# untitled.net
KiCad netlist of a schematic drawn in EAGLE
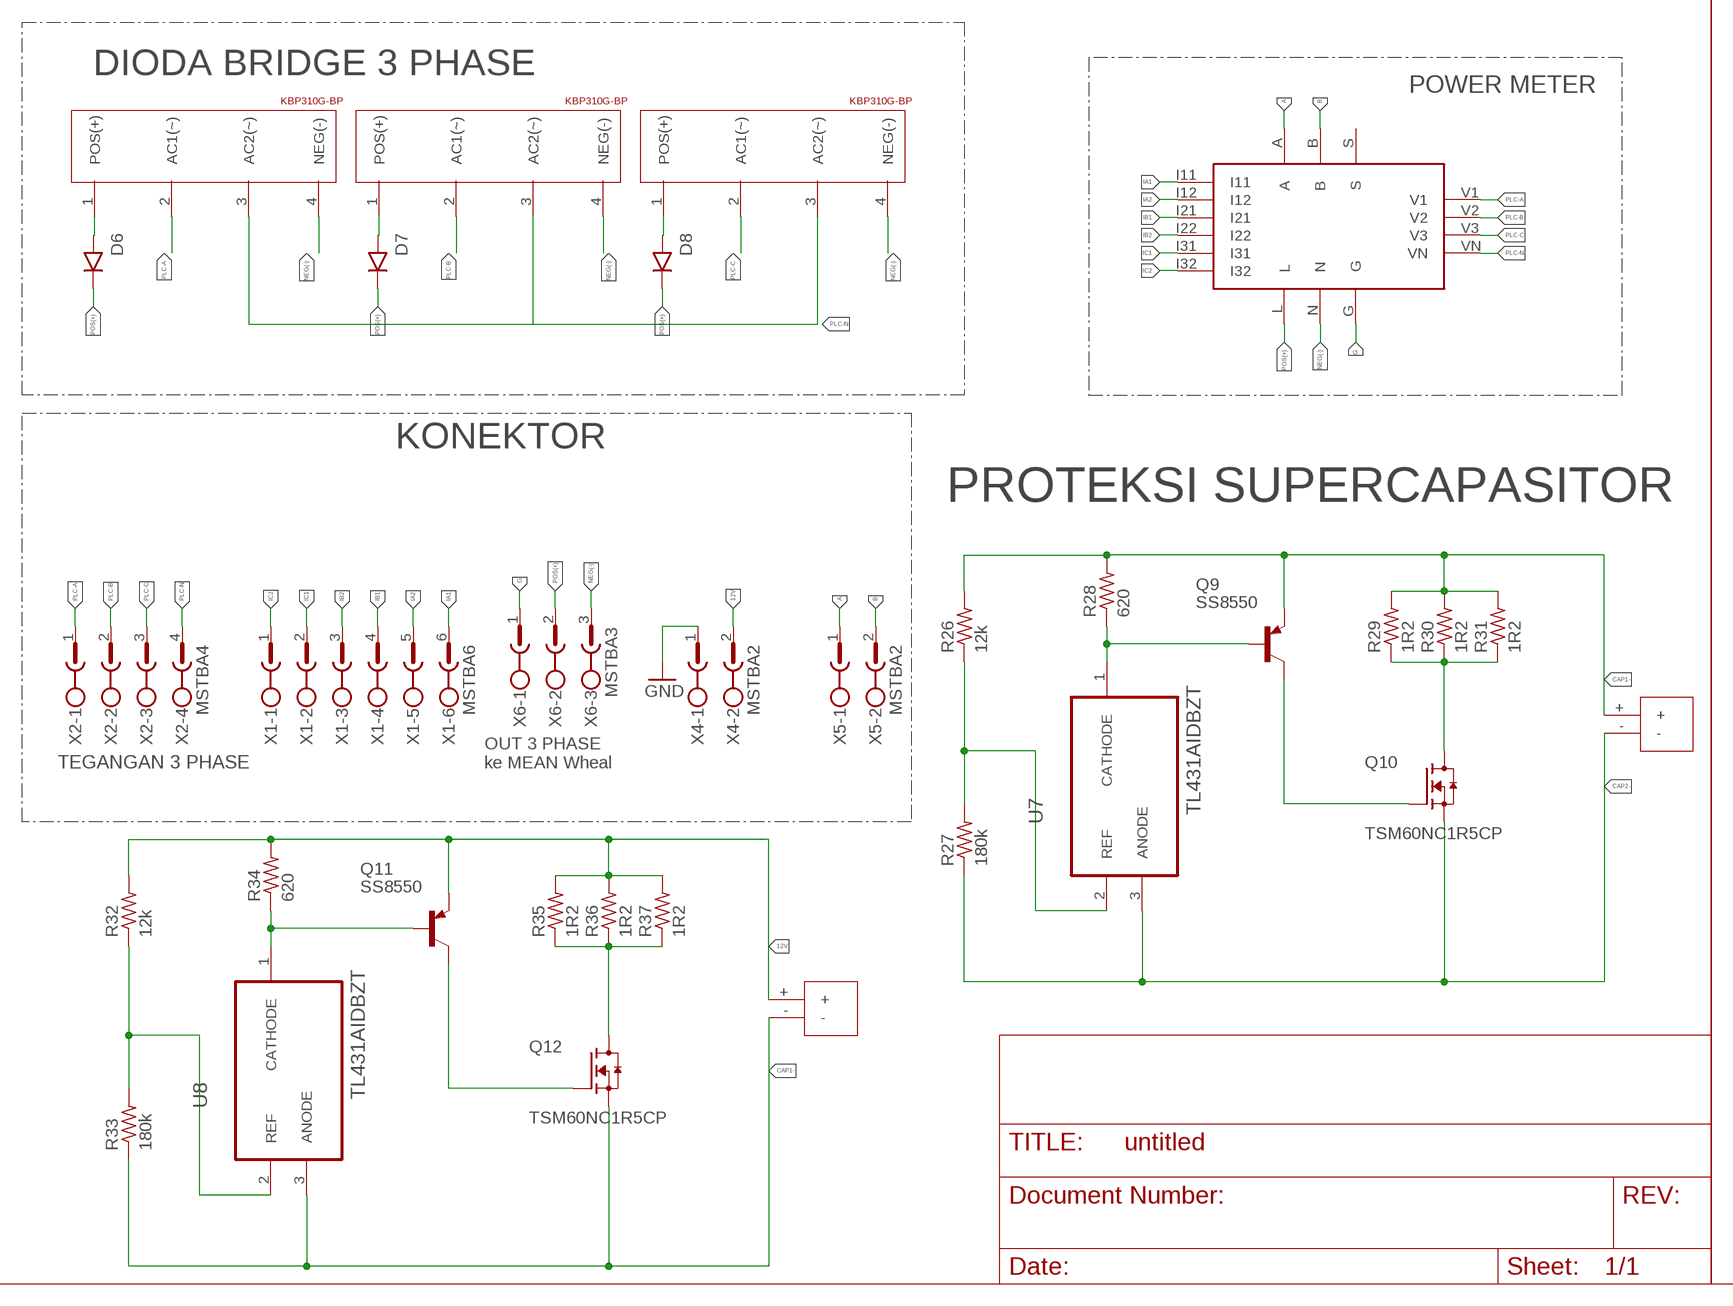
[diagram p0: schematic, sheet 1, part 1 of 2]
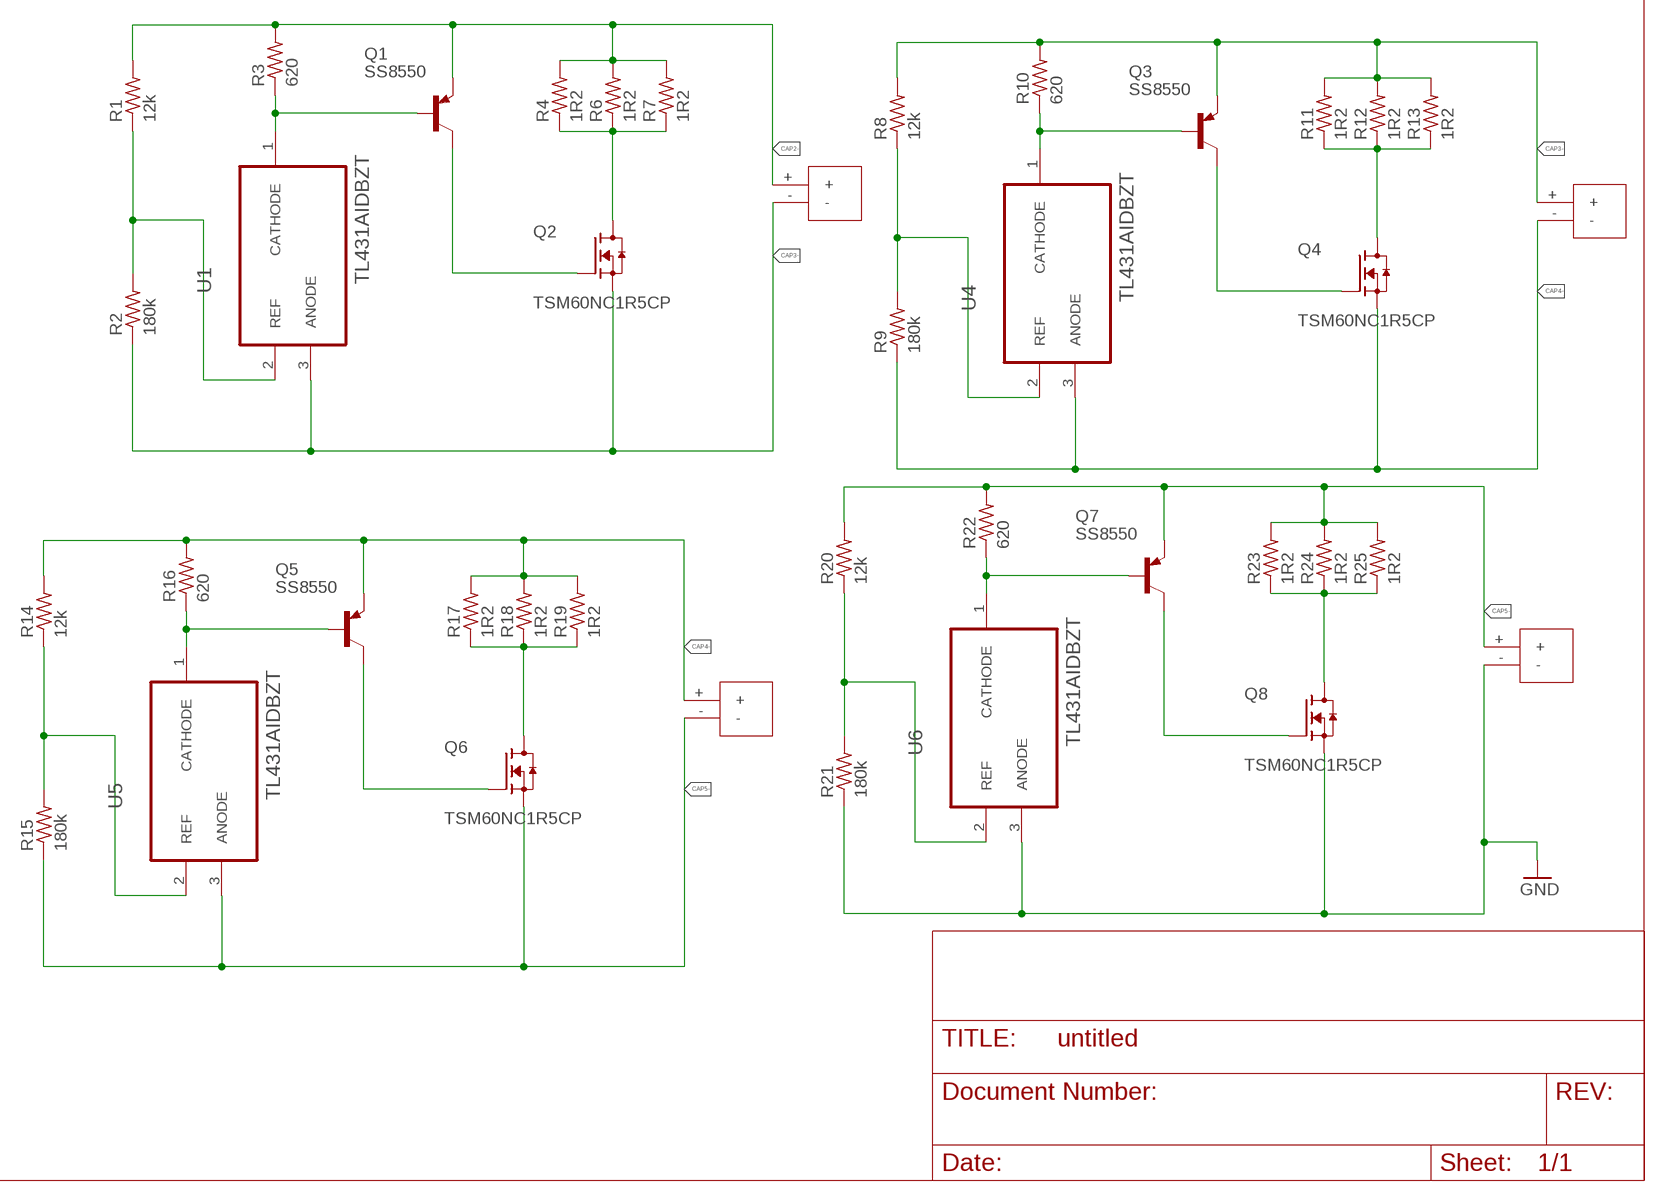
[diagram p1: schematic, sheet 1, part 2 of 2]

(export (version "E")
  (design (tool "Eeschema 10.0.6"))
  (components
    (comp (ref "D6")
      (value "1N4001")
      (footprint "eagle-import:DO41-10")
      (fields (field (name "MF") "HVCA"))
      (libsource (lib "eagle-import") (part "1N4001"))
    )
    (comp (ref "D7")
      (value "1N4001")
      (footprint "eagle-import:DO41-10")
      (fields (field (name "MF") "HVCA"))
      (libsource (lib "eagle-import") (part "1N4001"))
    )
    (comp (ref "D8")
      (value "1N4001")
      (footprint "eagle-import:DO41-10")
      (fields (field (name "MF") "HVCA"))
      (libsource (lib "eagle-import") (part "1N4001"))
    )
    (comp (ref "POWERMETER1")
      (value "POWERMETER")
      (footprint "eagle-import:POWERMETER")
      (libsource (lib "eagle-import") (part "POWERMETER"))
    )
    (comp (ref "Q1")
      (value "SS8550")
      (footprint "eagle-import:SOT-23_BEC")
      (fields (field (name "MF") "ON Semiconductor / Fairchild"))
      (libsource (lib "eagle-import") (part "SS8550"))
    )
    (comp (ref "Q2")
      (value "TSM60NC1R5CP")
      (footprint "eagle-import:TRANS_TSM60NC1R5CP")
      (fields (field (name "MF") "Taiwan Semiconductor"))
      (libsource (lib "eagle-import") (part "TSM60NC1R5CP"))
    )
    (comp (ref "Q3")
      (value "SS8550")
      (footprint "eagle-import:SOT-23_BEC")
      (fields (field (name "MF") "ON Semiconductor / Fairchild"))
      (libsource (lib "eagle-import") (part "SS8550"))
    )
    (comp (ref "Q4")
      (value "TSM60NC1R5CP")
      (footprint "eagle-import:TRANS_TSM60NC1R5CP")
      (fields (field (name "MF") "Taiwan Semiconductor"))
      (libsource (lib "eagle-import") (part "TSM60NC1R5CP"))
    )
    (comp (ref "Q5")
      (value "SS8550")
      (footprint "eagle-import:SOT-23_BEC")
      (fields (field (name "MF") "ON Semiconductor / Fairchild"))
      (libsource (lib "eagle-import") (part "SS8550"))
    )
    (comp (ref "Q6")
      (value "TSM60NC1R5CP")
      (footprint "eagle-import:TRANS_TSM60NC1R5CP")
      (fields (field (name "MF") "Taiwan Semiconductor"))
      (libsource (lib "eagle-import") (part "TSM60NC1R5CP"))
    )
    (comp (ref "Q7")
      (value "SS8550")
      (footprint "eagle-import:SOT-23_BEC")
      (fields (field (name "MF") "ON Semiconductor / Fairchild"))
      (libsource (lib "eagle-import") (part "SS8550"))
    )
    (comp (ref "Q8")
      (value "TSM60NC1R5CP")
      (footprint "eagle-import:TRANS_TSM60NC1R5CP")
      (fields (field (name "MF") "Taiwan Semiconductor"))
      (libsource (lib "eagle-import") (part "TSM60NC1R5CP"))
    )
    (comp (ref "Q9")
      (value "SS8550")
      (footprint "eagle-import:SOT-23_BEC")
      (fields (field (name "MF") "ON Semiconductor / Fairchild"))
      (libsource (lib "eagle-import") (part "SS8550"))
    )
    (comp (ref "Q10")
      (value "TSM60NC1R5CP")
      (footprint "eagle-import:TRANS_TSM60NC1R5CP")
      (fields (field (name "MF") "Taiwan Semiconductor"))
      (libsource (lib "eagle-import") (part "TSM60NC1R5CP"))
    )
    (comp (ref "Q11")
      (value "SS8550")
      (footprint "eagle-import:SOT-23_BEC")
      (fields (field (name "MF") "ON Semiconductor / Fairchild"))
      (libsource (lib "eagle-import") (part "SS8550"))
    )
    (comp (ref "Q12")
      (value "TSM60NC1R5CP")
      (footprint "eagle-import:TRANS_TSM60NC1R5CP")
      (fields (field (name "MF") "Taiwan Semiconductor"))
      (libsource (lib "eagle-import") (part "TSM60NC1R5CP"))
    )
    (comp (ref "R1")
      (value "12k")
      (footprint "eagle-import:R0805")
      (libsource (lib "eagle-import") (part "R-US_R0805"))
    )
    (comp (ref "R2")
      (value "180k")
      (footprint "eagle-import:R0805")
      (libsource (lib "eagle-import") (part "R-US_R0805"))
    )
    (comp (ref "R3")
      (value "620")
      (footprint "eagle-import:R0805")
      (libsource (lib "eagle-import") (part "R-US_R0805"))
    )
    (comp (ref "R4")
      (value "1R2")
      (footprint "eagle-import:R2512")
      (libsource (lib "eagle-import") (part "rcl_334_R-US_R2512"))
    )
    (comp (ref "R6")
      (value "1R2")
      (footprint "eagle-import:R2512")
      (libsource (lib "eagle-import") (part "rcl_334_R-US_R2512"))
    )
    (comp (ref "R7")
      (value "1R2")
      (footprint "eagle-import:R2512")
      (libsource (lib "eagle-import") (part "rcl_334_R-US_R2512"))
    )
    (comp (ref "R8")
      (value "12k")
      (footprint "eagle-import:R0805")
      (libsource (lib "eagle-import") (part "R-US_R0805"))
    )
    (comp (ref "R9")
      (value "180k")
      (footprint "eagle-import:R0805")
      (libsource (lib "eagle-import") (part "R-US_R0805"))
    )
    (comp (ref "R10")
      (value "620")
      (footprint "eagle-import:R0805")
      (libsource (lib "eagle-import") (part "R-US_R0805"))
    )
    (comp (ref "R11")
      (value "1R2")
      (footprint "eagle-import:R2512")
      (libsource (lib "eagle-import") (part "rcl_334_R-US_R2512"))
    )
    (comp (ref "R12")
      (value "1R2")
      (footprint "eagle-import:R2512")
      (libsource (lib "eagle-import") (part "rcl_334_R-US_R2512"))
    )
    (comp (ref "R13")
      (value "1R2")
      (footprint "eagle-import:R2512")
      (libsource (lib "eagle-import") (part "rcl_334_R-US_R2512"))
    )
    (comp (ref "R14")
      (value "12k")
      (footprint "eagle-import:R0805")
      (libsource (lib "eagle-import") (part "R-US_R0805"))
    )
    (comp (ref "R15")
      (value "180k")
      (footprint "eagle-import:R0805")
      (libsource (lib "eagle-import") (part "R-US_R0805"))
    )
    (comp (ref "R16")
      (value "620")
      (footprint "eagle-import:R0805")
      (libsource (lib "eagle-import") (part "R-US_R0805"))
    )
    (comp (ref "R17")
      (value "1R2")
      (footprint "eagle-import:R2512")
      (libsource (lib "eagle-import") (part "rcl_334_R-US_R2512"))
    )
    (comp (ref "R18")
      (value "1R2")
      (footprint "eagle-import:R2512")
      (libsource (lib "eagle-import") (part "rcl_334_R-US_R2512"))
    )
    (comp (ref "R19")
      (value "1R2")
      (footprint "eagle-import:R2512")
      (libsource (lib "eagle-import") (part "rcl_334_R-US_R2512"))
    )
    (comp (ref "R20")
      (value "12k")
      (footprint "eagle-import:R0805")
      (libsource (lib "eagle-import") (part "R-US_R0805"))
    )
    (comp (ref "R21")
      (value "180k")
      (footprint "eagle-import:R0805")
      (libsource (lib "eagle-import") (part "R-US_R0805"))
    )
    (comp (ref "R22")
      (value "620")
      (footprint "eagle-import:R0805")
      (libsource (lib "eagle-import") (part "R-US_R0805"))
    )
    (comp (ref "R23")
      (value "1R2")
      (footprint "eagle-import:R2512")
      (libsource (lib "eagle-import") (part "rcl_334_R-US_R2512"))
    )
    (comp (ref "R24")
      (value "1R2")
      (footprint "eagle-import:R2512")
      (libsource (lib "eagle-import") (part "rcl_334_R-US_R2512"))
    )
    (comp (ref "R25")
      (value "1R2")
      (footprint "eagle-import:R2512")
      (libsource (lib "eagle-import") (part "rcl_334_R-US_R2512"))
    )
    (comp (ref "R26")
      (value "12k")
      (footprint "eagle-import:R0805")
      (libsource (lib "eagle-import") (part "R-US_R0805"))
    )
    (comp (ref "R27")
      (value "180k")
      (footprint "eagle-import:R0805")
      (libsource (lib "eagle-import") (part "R-US_R0805"))
    )
    (comp (ref "R28")
      (value "620")
      (footprint "eagle-import:R0805")
      (libsource (lib "eagle-import") (part "R-US_R0805"))
    )
    (comp (ref "R29")
      (value "1R2")
      (footprint "eagle-import:R2512")
      (libsource (lib "eagle-import") (part "rcl_334_R-US_R2512"))
    )
    (comp (ref "R30")
      (value "1R2")
      (footprint "eagle-import:R2512")
      (libsource (lib "eagle-import") (part "rcl_334_R-US_R2512"))
    )
    (comp (ref "R31")
      (value "1R2")
      (footprint "eagle-import:R2512")
      (libsource (lib "eagle-import") (part "rcl_334_R-US_R2512"))
    )
    (comp (ref "R32")
      (value "12k")
      (footprint "eagle-import:R0805")
      (libsource (lib "eagle-import") (part "R-US_R0805"))
    )
    (comp (ref "R33")
      (value "180k")
      (footprint "eagle-import:R0805")
      (libsource (lib "eagle-import") (part "R-US_R0805"))
    )
    (comp (ref "R34")
      (value "620")
      (footprint "eagle-import:R0805")
      (libsource (lib "eagle-import") (part "R-US_R0805"))
    )
    (comp (ref "R35")
      (value "1R2")
      (footprint "eagle-import:R2512")
      (libsource (lib "eagle-import") (part "rcl_334_R-US_R2512"))
    )
    (comp (ref "R36")
      (value "1R2")
      (footprint "eagle-import:R2512")
      (libsource (lib "eagle-import") (part "rcl_334_R-US_R2512"))
    )
    (comp (ref "R37")
      (value "1R2")
      (footprint "eagle-import:R2512")
      (libsource (lib "eagle-import") (part "rcl_334_R-US_R2512"))
    )
    (comp (ref "SUPERCAP1")
      (value "2.7/500F")
      (footprint "eagle-import:SUPERCAP")
      (libsource (lib "eagle-import") (part "SUPERCAP"))
    )
    (comp (ref "SUPERCAP2")
      (value "2.7/500F")
      (footprint "eagle-import:SUPERCAP")
      (libsource (lib "eagle-import") (part "SUPERCAP"))
    )
    (comp (ref "SUPERCAP3")
      (value "2.7/500F")
      (footprint "eagle-import:SUPERCAP")
      (libsource (lib "eagle-import") (part "SUPERCAP"))
    )
    (comp (ref "SUPERCAP4")
      (value "2.7/500F")
      (footprint "eagle-import:SUPERCAP")
      (libsource (lib "eagle-import") (part "SUPERCAP"))
    )
    (comp (ref "SUPERCAP5")
      (value "2.7/500F")
      (footprint "eagle-import:SUPERCAP")
      (libsource (lib "eagle-import") (part "SUPERCAP"))
    )
    (comp (ref "SUPERCAP6")
      (value "2.7/500F")
      (footprint "eagle-import:SUPERCAP")
      (libsource (lib "eagle-import") (part "SUPERCAP"))
    )
    (comp (ref "U$1")
      (value "KBP310G-BP")
      (footprint "eagle-import:KBP310G-BP")
      (fields (field (name "MF") "Micro Commercial"))
      (libsource (lib "eagle-import") (part "KBP310G-BP"))
    )
    (comp (ref "U$2")
      (value "KBP310G-BP")
      (footprint "eagle-import:KBP310G-BP")
      (fields (field (name "MF") "Micro Commercial"))
      (libsource (lib "eagle-import") (part "KBP310G-BP"))
    )
    (comp (ref "U$3")
      (value "KBP310G-BP")
      (footprint "eagle-import:KBP310G-BP")
      (fields (field (name "MF") "Micro Commercial"))
      (libsource (lib "eagle-import") (part "KBP310G-BP"))
    )
    (comp (ref "U1")
      (value "TL431AIDBZT")
      (footprint "eagle-import:SOT95P237X112-3N")
      (fields (field (name "MF") "Texas Instruments"))
      (libsource (lib "eagle-import") (part "TL431AIDBZT"))
    )
    (comp (ref "U4")
      (value "TL431AIDBZT")
      (footprint "eagle-import:SOT95P237X112-3N")
      (fields (field (name "MF") "Texas Instruments"))
      (libsource (lib "eagle-import") (part "TL431AIDBZT"))
    )
    (comp (ref "U5")
      (value "TL431AIDBZT")
      (footprint "eagle-import:SOT95P237X112-3N")
      (fields (field (name "MF") "Texas Instruments"))
      (libsource (lib "eagle-import") (part "TL431AIDBZT"))
    )
    (comp (ref "U6")
      (value "TL431AIDBZT")
      (footprint "eagle-import:SOT95P237X112-3N")
      (fields (field (name "MF") "Texas Instruments"))
      (libsource (lib "eagle-import") (part "TL431AIDBZT"))
    )
    (comp (ref "U7")
      (value "TL431AIDBZT")
      (footprint "eagle-import:SOT95P237X112-3N")
      (fields (field (name "MF") "Texas Instruments"))
      (libsource (lib "eagle-import") (part "TL431AIDBZT"))
    )
    (comp (ref "U8")
      (value "TL431AIDBZT")
      (footprint "eagle-import:SOT95P237X112-3N")
      (fields (field (name "MF") "Texas Instruments"))
      (libsource (lib "eagle-import") (part "TL431AIDBZT"))
    )
    (comp (ref "X1")
      (value "MSTBA6")
      (footprint "eagle-import:MSTBA6")
      (fields (field (name "MF") "FARNELL") (field (name "MPN") "1757284"))
      (libsource (lib "eagle-import") (part "MSTBA6"))
    )
    (comp (ref "X2")
      (value "MSTBA4")
      (footprint "eagle-import:MSTBA4")
      (fields (field (name "MF") "FARNELL") (field (name "MPN") "1757268"))
      (libsource (lib "eagle-import") (part "MSTBA4"))
    )
    (comp (ref "X4")
      (value "MSTBA2")
      (footprint "eagle-import:MSTBA2")
      (fields (field (name "MF") "FARNELL") (field (name "MPN") "1757242"))
      (libsource (lib "eagle-import") (part "MSTBA2"))
    )
    (comp (ref "X5")
      (value "MSTBA2")
      (footprint "eagle-import:MSTBA2")
      (fields (field (name "MF") "FARNELL") (field (name "MPN") "1757242"))
      (libsource (lib "eagle-import") (part "MSTBA2"))
    )
    (comp (ref "X6")
      (value "MSTBA3")
      (footprint "eagle-import:MSTBA3")
      (fields (field (name "MF") "FARNELL") (field (name "MPN") "1757255"))
      (libsource (lib "eagle-import") (part "MSTBA3"))
    )
  )
  (nets
    (net (code "1") (name "12V") (class "Default")
      (node (ref "Q11") (pin "E") (pinfunction "E_E") (pintype "passive"))
      (node (ref "R32") (pin "2") (pinfunction "2_2") (pintype "passive"))
      (node (ref "R34") (pin "2") (pinfunction "2_2") (pintype "passive"))
      (node (ref "R35") (pin "2") (pinfunction "2_2") (pintype "passive"))
      (node (ref "R36") (pin "2") (pinfunction "2_2") (pintype "passive"))
      (node (ref "R37") (pin "2") (pinfunction "2_2") (pintype "passive"))
      (node (ref "SUPERCAP6") (pin "+") (pinfunction "+_+") (pintype "bidirectional"))
      (node (ref "X4") (pin "2") (pinfunction "1_2") (pintype "passive"))
    )
    (net (code "2") (name "A") (class "Default")
      (node (ref "POWERMETER1") (pin "A") (pinfunction "A_A") (pintype "bidirectional"))
      (node (ref "X5") (pin "1") (pinfunction "1_1") (pintype "passive"))
    )
    (net (code "3") (name "B") (class "Default")
      (node (ref "POWERMETER1") (pin "B") (pinfunction "B_B") (pintype "bidirectional"))
      (node (ref "X5") (pin "2") (pinfunction "1_2") (pintype "passive"))
    )
    (net (code "4") (name "CAP1-") (class "Default")
      (node (ref "Q12") (pin "3") (pinfunction "S_3") (pintype "passive"))
      (node (ref "Q9") (pin "E") (pinfunction "E_E") (pintype "passive"))
      (node (ref "R26") (pin "2") (pinfunction "2_2") (pintype "passive"))
      (node (ref "R28") (pin "2") (pinfunction "2_2") (pintype "passive"))
      (node (ref "R29") (pin "2") (pinfunction "2_2") (pintype "passive"))
      (node (ref "R30") (pin "2") (pinfunction "2_2") (pintype "passive"))
      (node (ref "R31") (pin "2") (pinfunction "2_2") (pintype "passive"))
      (node (ref "R33") (pin "1") (pinfunction "1_1") (pintype "passive"))
      (node (ref "SUPERCAP5") (pin "+") (pinfunction "+_+") (pintype "bidirectional"))
      (node (ref "SUPERCAP6") (pin "-") (pinfunction "-_-") (pintype "bidirectional"))
      (node (ref "U8") (pin "3") (pinfunction "ANODE_3") (pintype "passive"))
    )
    (net (code "5") (name "CAP2-") (class "Default")
      (node (ref "Q1") (pin "E") (pinfunction "E_E") (pintype "passive"))
      (node (ref "Q10") (pin "3") (pinfunction "S_3") (pintype "passive"))
      (node (ref "R1") (pin "2") (pinfunction "2_2") (pintype "passive"))
      (node (ref "R27") (pin "1") (pinfunction "1_1") (pintype "passive"))
      (node (ref "R3") (pin "2") (pinfunction "2_2") (pintype "passive"))
      (node (ref "R4") (pin "2") (pinfunction "2_2") (pintype "passive"))
      (node (ref "R6") (pin "2") (pinfunction "2_2") (pintype "passive"))
      (node (ref "R7") (pin "2") (pinfunction "2_2") (pintype "passive"))
      (node (ref "SUPERCAP1") (pin "+") (pinfunction "+_+") (pintype "bidirectional"))
      (node (ref "SUPERCAP5") (pin "-") (pinfunction "-_-") (pintype "bidirectional"))
      (node (ref "U7") (pin "3") (pinfunction "ANODE_3") (pintype "passive"))
    )
    (net (code "6") (name "CAP3-") (class "Default")
      (node (ref "Q2") (pin "3") (pinfunction "S_3") (pintype "passive"))
      (node (ref "Q3") (pin "E") (pinfunction "E_E") (pintype "passive"))
      (node (ref "R10") (pin "2") (pinfunction "2_2") (pintype "passive"))
      (node (ref "R11") (pin "2") (pinfunction "2_2") (pintype "passive"))
      (node (ref "R12") (pin "2") (pinfunction "2_2") (pintype "passive"))
      (node (ref "R13") (pin "2") (pinfunction "2_2") (pintype "passive"))
      (node (ref "R2") (pin "1") (pinfunction "1_1") (pintype "passive"))
      (node (ref "R8") (pin "2") (pinfunction "2_2") (pintype "passive"))
      (node (ref "SUPERCAP1") (pin "-") (pinfunction "-_-") (pintype "bidirectional"))
      (node (ref "SUPERCAP2") (pin "+") (pinfunction "+_+") (pintype "bidirectional"))
      (node (ref "U1") (pin "3") (pinfunction "ANODE_3") (pintype "passive"))
    )
    (net (code "7") (name "CAP4-") (class "Default")
      (node (ref "Q4") (pin "3") (pinfunction "S_3") (pintype "passive"))
      (node (ref "Q5") (pin "E") (pinfunction "E_E") (pintype "passive"))
      (node (ref "R14") (pin "2") (pinfunction "2_2") (pintype "passive"))
      (node (ref "R16") (pin "2") (pinfunction "2_2") (pintype "passive"))
      (node (ref "R17") (pin "2") (pinfunction "2_2") (pintype "passive"))
      (node (ref "R18") (pin "2") (pinfunction "2_2") (pintype "passive"))
      (node (ref "R19") (pin "2") (pinfunction "2_2") (pintype "passive"))
      (node (ref "R9") (pin "1") (pinfunction "1_1") (pintype "passive"))
      (node (ref "SUPERCAP2") (pin "-") (pinfunction "-_-") (pintype "bidirectional"))
      (node (ref "SUPERCAP3") (pin "+") (pinfunction "+_+") (pintype "bidirectional"))
      (node (ref "U4") (pin "3") (pinfunction "ANODE_3") (pintype "passive"))
    )
    (net (code "8") (name "CAP5-") (class "Default")
      (node (ref "Q6") (pin "3") (pinfunction "S_3") (pintype "passive"))
      (node (ref "Q7") (pin "E") (pinfunction "E_E") (pintype "passive"))
      (node (ref "R15") (pin "1") (pinfunction "1_1") (pintype "passive"))
      (node (ref "R20") (pin "2") (pinfunction "2_2") (pintype "passive"))
      (node (ref "R22") (pin "2") (pinfunction "2_2") (pintype "passive"))
      (node (ref "R23") (pin "2") (pinfunction "2_2") (pintype "passive"))
      (node (ref "R24") (pin "2") (pinfunction "2_2") (pintype "passive"))
      (node (ref "R25") (pin "2") (pinfunction "2_2") (pintype "passive"))
      (node (ref "SUPERCAP3") (pin "-") (pinfunction "-_-") (pintype "bidirectional"))
      (node (ref "SUPERCAP4") (pin "+") (pinfunction "+_+") (pintype "bidirectional"))
      (node (ref "U5") (pin "3") (pinfunction "ANODE_3") (pintype "passive"))
    )
    (net (code "9") (name "G") (class "Default")
      (node (ref "POWERMETER1") (pin "G") (pinfunction "G_G") (pintype "bidirectional"))
      (node (ref "X6") (pin "1") (pinfunction "1_1") (pintype "passive"))
    )
    (net (code "10") (name "GND") (class "Default")
      (node (ref "Q8") (pin "3") (pinfunction "S_3") (pintype "passive"))
      (node (ref "R21") (pin "1") (pinfunction "1_1") (pintype "passive"))
      (node (ref "SUPERCAP4") (pin "-") (pinfunction "-_-") (pintype "bidirectional"))
      (node (ref "U6") (pin "3") (pinfunction "ANODE_3") (pintype "passive"))
      (node (ref "X4") (pin "1") (pinfunction "1_1") (pintype "passive"))
    )
    (net (code "11") (name "IA1") (class "Default")
      (node (ref "POWERMETER1") (pin "I11") (pinfunction "I11_I11") (pintype "bidirectional"))
      (node (ref "X1") (pin "6") (pinfunction "1_6") (pintype "passive"))
    )
    (net (code "12") (name "IA2") (class "Default")
      (node (ref "POWERMETER1") (pin "I12") (pinfunction "I12_I12") (pintype "bidirectional"))
      (node (ref "X1") (pin "5") (pinfunction "1_5") (pintype "passive"))
    )
    (net (code "13") (name "IB1") (class "Default")
      (node (ref "POWERMETER1") (pin "I21") (pinfunction "I21_I21") (pintype "bidirectional"))
      (node (ref "X1") (pin "4") (pinfunction "1_4") (pintype "passive"))
    )
    (net (code "14") (name "IB2") (class "Default")
      (node (ref "POWERMETER1") (pin "I22") (pinfunction "I22_I22") (pintype "bidirectional"))
      (node (ref "X1") (pin "3") (pinfunction "1_3") (pintype "passive"))
    )
    (net (code "15") (name "IC1") (class "Default")
      (node (ref "POWERMETER1") (pin "I31") (pinfunction "I31_I31") (pintype "bidirectional"))
      (node (ref "X1") (pin "2") (pinfunction "1_2") (pintype "passive"))
    )
    (net (code "16") (name "IC2") (class "Default")
      (node (ref "POWERMETER1") (pin "I32") (pinfunction "I32_I32") (pintype "bidirectional"))
      (node (ref "X1") (pin "1") (pinfunction "1_1") (pintype "passive"))
    )
    (net (code "17") (name "NEG(-)") (class "Default")
      (node (ref "POWERMETER1") (pin "N") (pinfunction "N_N") (pintype "bidirectional"))
      (node (ref "U$1") (pin "4") (pinfunction "NEG(-)_4") (pintype "bidirectional"))
      (node (ref "U$2") (pin "4") (pinfunction "NEG(-)_4") (pintype "bidirectional"))
      (node (ref "U$3") (pin "4") (pinfunction "NEG(-)_4") (pintype "bidirectional"))
      (node (ref "X6") (pin "3") (pinfunction "1_3") (pintype "passive"))
    )
    (net (code "18") (name "Net-(D6-ANODE)") (class "Default")
      (node (ref "D6") (pin "A") (pinfunction "ANODE_A") (pintype "passive"))
      (node (ref "U$1") (pin "1") (pinfunction "POS(+)_1") (pintype "bidirectional"))
    )
    (net (code "19") (name "Net-(D7-ANODE)") (class "Default")
      (node (ref "D7") (pin "A") (pinfunction "ANODE_A") (pintype "passive"))
      (node (ref "U$2") (pin "1") (pinfunction "POS(+)_1") (pintype "bidirectional"))
    )
    (net (code "20") (name "Net-(D8-ANODE)") (class "Default")
      (node (ref "D8") (pin "A") (pinfunction "ANODE_A") (pintype "passive"))
      (node (ref "U$3") (pin "1") (pinfunction "POS(+)_1") (pintype "bidirectional"))
    )
    (net (code "21") (name "Net-(Q2-D)") (class "Default")
      (node (ref "Q2") (pin "2") (pinfunction "D_2") (pintype "passive"))
      (node (ref "R4") (pin "1") (pinfunction "1_1") (pintype "passive"))
      (node (ref "R6") (pin "1") (pinfunction "1_1") (pintype "passive"))
      (node (ref "R7") (pin "1") (pinfunction "1_1") (pintype "passive"))
    )
    (net (code "22") (name "Net-(Q2-G)") (class "Default")
      (node (ref "Q1") (pin "C") (pinfunction "C_C") (pintype "passive"))
      (node (ref "Q2") (pin "1") (pinfunction "G_1") (pintype "passive"))
    )
    (net (code "23") (name "Net-(Q4-D)") (class "Default")
      (node (ref "Q4") (pin "2") (pinfunction "D_2") (pintype "passive"))
      (node (ref "R11") (pin "1") (pinfunction "1_1") (pintype "passive"))
      (node (ref "R12") (pin "1") (pinfunction "1_1") (pintype "passive"))
      (node (ref "R13") (pin "1") (pinfunction "1_1") (pintype "passive"))
    )
    (net (code "24") (name "Net-(Q4-G)") (class "Default")
      (node (ref "Q3") (pin "C") (pinfunction "C_C") (pintype "passive"))
      (node (ref "Q4") (pin "1") (pinfunction "G_1") (pintype "passive"))
    )
    (net (code "25") (name "Net-(Q6-D)") (class "Default")
      (node (ref "Q6") (pin "2") (pinfunction "D_2") (pintype "passive"))
      (node (ref "R17") (pin "1") (pinfunction "1_1") (pintype "passive"))
      (node (ref "R18") (pin "1") (pinfunction "1_1") (pintype "passive"))
      (node (ref "R19") (pin "1") (pinfunction "1_1") (pintype "passive"))
    )
    (net (code "26") (name "Net-(Q6-G)") (class "Default")
      (node (ref "Q5") (pin "C") (pinfunction "C_C") (pintype "passive"))
      (node (ref "Q6") (pin "1") (pinfunction "G_1") (pintype "passive"))
    )
    (net (code "27") (name "Net-(Q8-D)") (class "Default")
      (node (ref "Q8") (pin "2") (pinfunction "D_2") (pintype "passive"))
      (node (ref "R23") (pin "1") (pinfunction "1_1") (pintype "passive"))
      (node (ref "R24") (pin "1") (pinfunction "1_1") (pintype "passive"))
      (node (ref "R25") (pin "1") (pinfunction "1_1") (pintype "passive"))
    )
    (net (code "28") (name "Net-(Q8-G)") (class "Default")
      (node (ref "Q7") (pin "C") (pinfunction "C_C") (pintype "passive"))
      (node (ref "Q8") (pin "1") (pinfunction "G_1") (pintype "passive"))
    )
    (net (code "29") (name "Net-(Q10-D)") (class "Default")
      (node (ref "Q10") (pin "2") (pinfunction "D_2") (pintype "passive"))
      (node (ref "R29") (pin "1") (pinfunction "1_1") (pintype "passive"))
      (node (ref "R30") (pin "1") (pinfunction "1_1") (pintype "passive"))
      (node (ref "R31") (pin "1") (pinfunction "1_1") (pintype "passive"))
    )
    (net (code "30") (name "Net-(Q10-G)") (class "Default")
      (node (ref "Q10") (pin "1") (pinfunction "G_1") (pintype "passive"))
      (node (ref "Q9") (pin "C") (pinfunction "C_C") (pintype "passive"))
    )
    (net (code "31") (name "Net-(Q12-D)") (class "Default")
      (node (ref "Q12") (pin "2") (pinfunction "D_2") (pintype "passive"))
      (node (ref "R35") (pin "1") (pinfunction "1_1") (pintype "passive"))
      (node (ref "R36") (pin "1") (pinfunction "1_1") (pintype "passive"))
      (node (ref "R37") (pin "1") (pinfunction "1_1") (pintype "passive"))
    )
    (net (code "32") (name "Net-(Q12-G)") (class "Default")
      (node (ref "Q11") (pin "C") (pinfunction "C_C") (pintype "passive"))
      (node (ref "Q12") (pin "1") (pinfunction "G_1") (pintype "passive"))
    )
    (net (code "33") (name "Net-(U1-CATHODE)") (class "Default")
      (node (ref "Q1") (pin "B") (pinfunction "B_B") (pintype "passive"))
      (node (ref "R3") (pin "1") (pinfunction "1_1") (pintype "passive"))
      (node (ref "U1") (pin "1") (pinfunction "CATHODE_1") (pintype "passive"))
    )
    (net (code "34") (name "Net-(U1-REF)") (class "Default")
      (node (ref "R1") (pin "1") (pinfunction "1_1") (pintype "passive"))
      (node (ref "R2") (pin "2") (pinfunction "2_2") (pintype "passive"))
      (node (ref "U1") (pin "2") (pinfunction "REF_2") (pintype "power_in"))
    )
    (net (code "35") (name "Net-(U4-CATHODE)") (class "Default")
      (node (ref "Q3") (pin "B") (pinfunction "B_B") (pintype "passive"))
      (node (ref "R10") (pin "1") (pinfunction "1_1") (pintype "passive"))
      (node (ref "U4") (pin "1") (pinfunction "CATHODE_1") (pintype "passive"))
    )
    (net (code "36") (name "Net-(U4-REF)") (class "Default")
      (node (ref "R8") (pin "1") (pinfunction "1_1") (pintype "passive"))
      (node (ref "R9") (pin "2") (pinfunction "2_2") (pintype "passive"))
      (node (ref "U4") (pin "2") (pinfunction "REF_2") (pintype "power_in"))
    )
    (net (code "37") (name "Net-(U5-CATHODE)") (class "Default")
      (node (ref "Q5") (pin "B") (pinfunction "B_B") (pintype "passive"))
      (node (ref "R16") (pin "1") (pinfunction "1_1") (pintype "passive"))
      (node (ref "U5") (pin "1") (pinfunction "CATHODE_1") (pintype "passive"))
    )
    (net (code "38") (name "Net-(U5-REF)") (class "Default")
      (node (ref "R14") (pin "1") (pinfunction "1_1") (pintype "passive"))
      (node (ref "R15") (pin "2") (pinfunction "2_2") (pintype "passive"))
      (node (ref "U5") (pin "2") (pinfunction "REF_2") (pintype "power_in"))
    )
    (net (code "39") (name "Net-(U6-CATHODE)") (class "Default")
      (node (ref "Q7") (pin "B") (pinfunction "B_B") (pintype "passive"))
      (node (ref "R22") (pin "1") (pinfunction "1_1") (pintype "passive"))
      (node (ref "U6") (pin "1") (pinfunction "CATHODE_1") (pintype "passive"))
    )
    (net (code "40") (name "Net-(U6-REF)") (class "Default")
      (node (ref "R20") (pin "1") (pinfunction "1_1") (pintype "passive"))
      (node (ref "R21") (pin "2") (pinfunction "2_2") (pintype "passive"))
      (node (ref "U6") (pin "2") (pinfunction "REF_2") (pintype "power_in"))
    )
    (net (code "41") (name "Net-(U7-CATHODE)") (class "Default")
      (node (ref "Q9") (pin "B") (pinfunction "B_B") (pintype "passive"))
      (node (ref "R28") (pin "1") (pinfunction "1_1") (pintype "passive"))
      (node (ref "U7") (pin "1") (pinfunction "CATHODE_1") (pintype "passive"))
    )
    (net (code "42") (name "Net-(U7-REF)") (class "Default")
      (node (ref "R26") (pin "1") (pinfunction "1_1") (pintype "passive"))
      (node (ref "R27") (pin "2") (pinfunction "2_2") (pintype "passive"))
      (node (ref "U7") (pin "2") (pinfunction "REF_2") (pintype "power_in"))
    )
    (net (code "43") (name "Net-(U8-CATHODE)") (class "Default")
      (node (ref "Q11") (pin "B") (pinfunction "B_B") (pintype "passive"))
      (node (ref "R34") (pin "1") (pinfunction "1_1") (pintype "passive"))
      (node (ref "U8") (pin "1") (pinfunction "CATHODE_1") (pintype "passive"))
    )
    (net (code "44") (name "Net-(U8-REF)") (class "Default")
      (node (ref "R32") (pin "1") (pinfunction "1_1") (pintype "passive"))
      (node (ref "R33") (pin "2") (pinfunction "2_2") (pintype "passive"))
      (node (ref "U8") (pin "2") (pinfunction "REF_2") (pintype "power_in"))
    )
    (net (code "45") (name "PLC-A") (class "Default")
      (node (ref "POWERMETER1") (pin "V1") (pinfunction "V1_V1") (pintype "bidirectional"))
      (node (ref "U$1") (pin "2") (pinfunction "AC1(~{})_2") (pintype "bidirectional"))
      (node (ref "X2") (pin "1") (pinfunction "1_1") (pintype "passive"))
    )
    (net (code "46") (name "PLC-B") (class "Default")
      (node (ref "POWERMETER1") (pin "V2") (pinfunction "V2_V2") (pintype "bidirectional"))
      (node (ref "U$2") (pin "2") (pinfunction "AC1(~{})_2") (pintype "bidirectional"))
      (node (ref "X2") (pin "2") (pinfunction "1_2") (pintype "passive"))
    )
    (net (code "47") (name "PLC-C") (class "Default")
      (node (ref "POWERMETER1") (pin "V3") (pinfunction "V3_V3") (pintype "bidirectional"))
      (node (ref "U$3") (pin "2") (pinfunction "AC1(~{})_2") (pintype "bidirectional"))
      (node (ref "X2") (pin "3") (pinfunction "1_3") (pintype "passive"))
    )
    (net (code "48") (name "PLC-N") (class "Default")
      (node (ref "POWERMETER1") (pin "VN") (pinfunction "VN_VN") (pintype "bidirectional"))
      (node (ref "U$1") (pin "3") (pinfunction "AC2(~{})_3") (pintype "bidirectional"))
      (node (ref "U$2") (pin "3") (pinfunction "AC2(~{})_3") (pintype "bidirectional"))
      (node (ref "U$3") (pin "3") (pinfunction "AC2(~{})_3") (pintype "bidirectional"))
      (node (ref "X2") (pin "4") (pinfunction "1_4") (pintype "passive"))
    )
    (net (code "49") (name "POS(+)") (class "Default")
      (node (ref "D6") (pin "C") (pinfunction "CATHODE_C") (pintype "passive"))
      (node (ref "D7") (pin "C") (pinfunction "CATHODE_C") (pintype "passive"))
      (node (ref "D8") (pin "C") (pinfunction "CATHODE_C") (pintype "passive"))
      (node (ref "POWERMETER1") (pin "L") (pinfunction "L_L") (pintype "bidirectional"))
      (node (ref "X6") (pin "2") (pinfunction "1_2") (pintype "passive"))
    )
    (net (code "50") (name "unconnected-(POWERMETER1-PadS)") (class "Default")
      (node (ref "POWERMETER1") (pin "S") (pinfunction "S_S") (pintype "bidirectional"))
    )
  )
)
